# PCB_Schematic_V1.net
KiCad netlist of a schematic drawn in EasyEDA
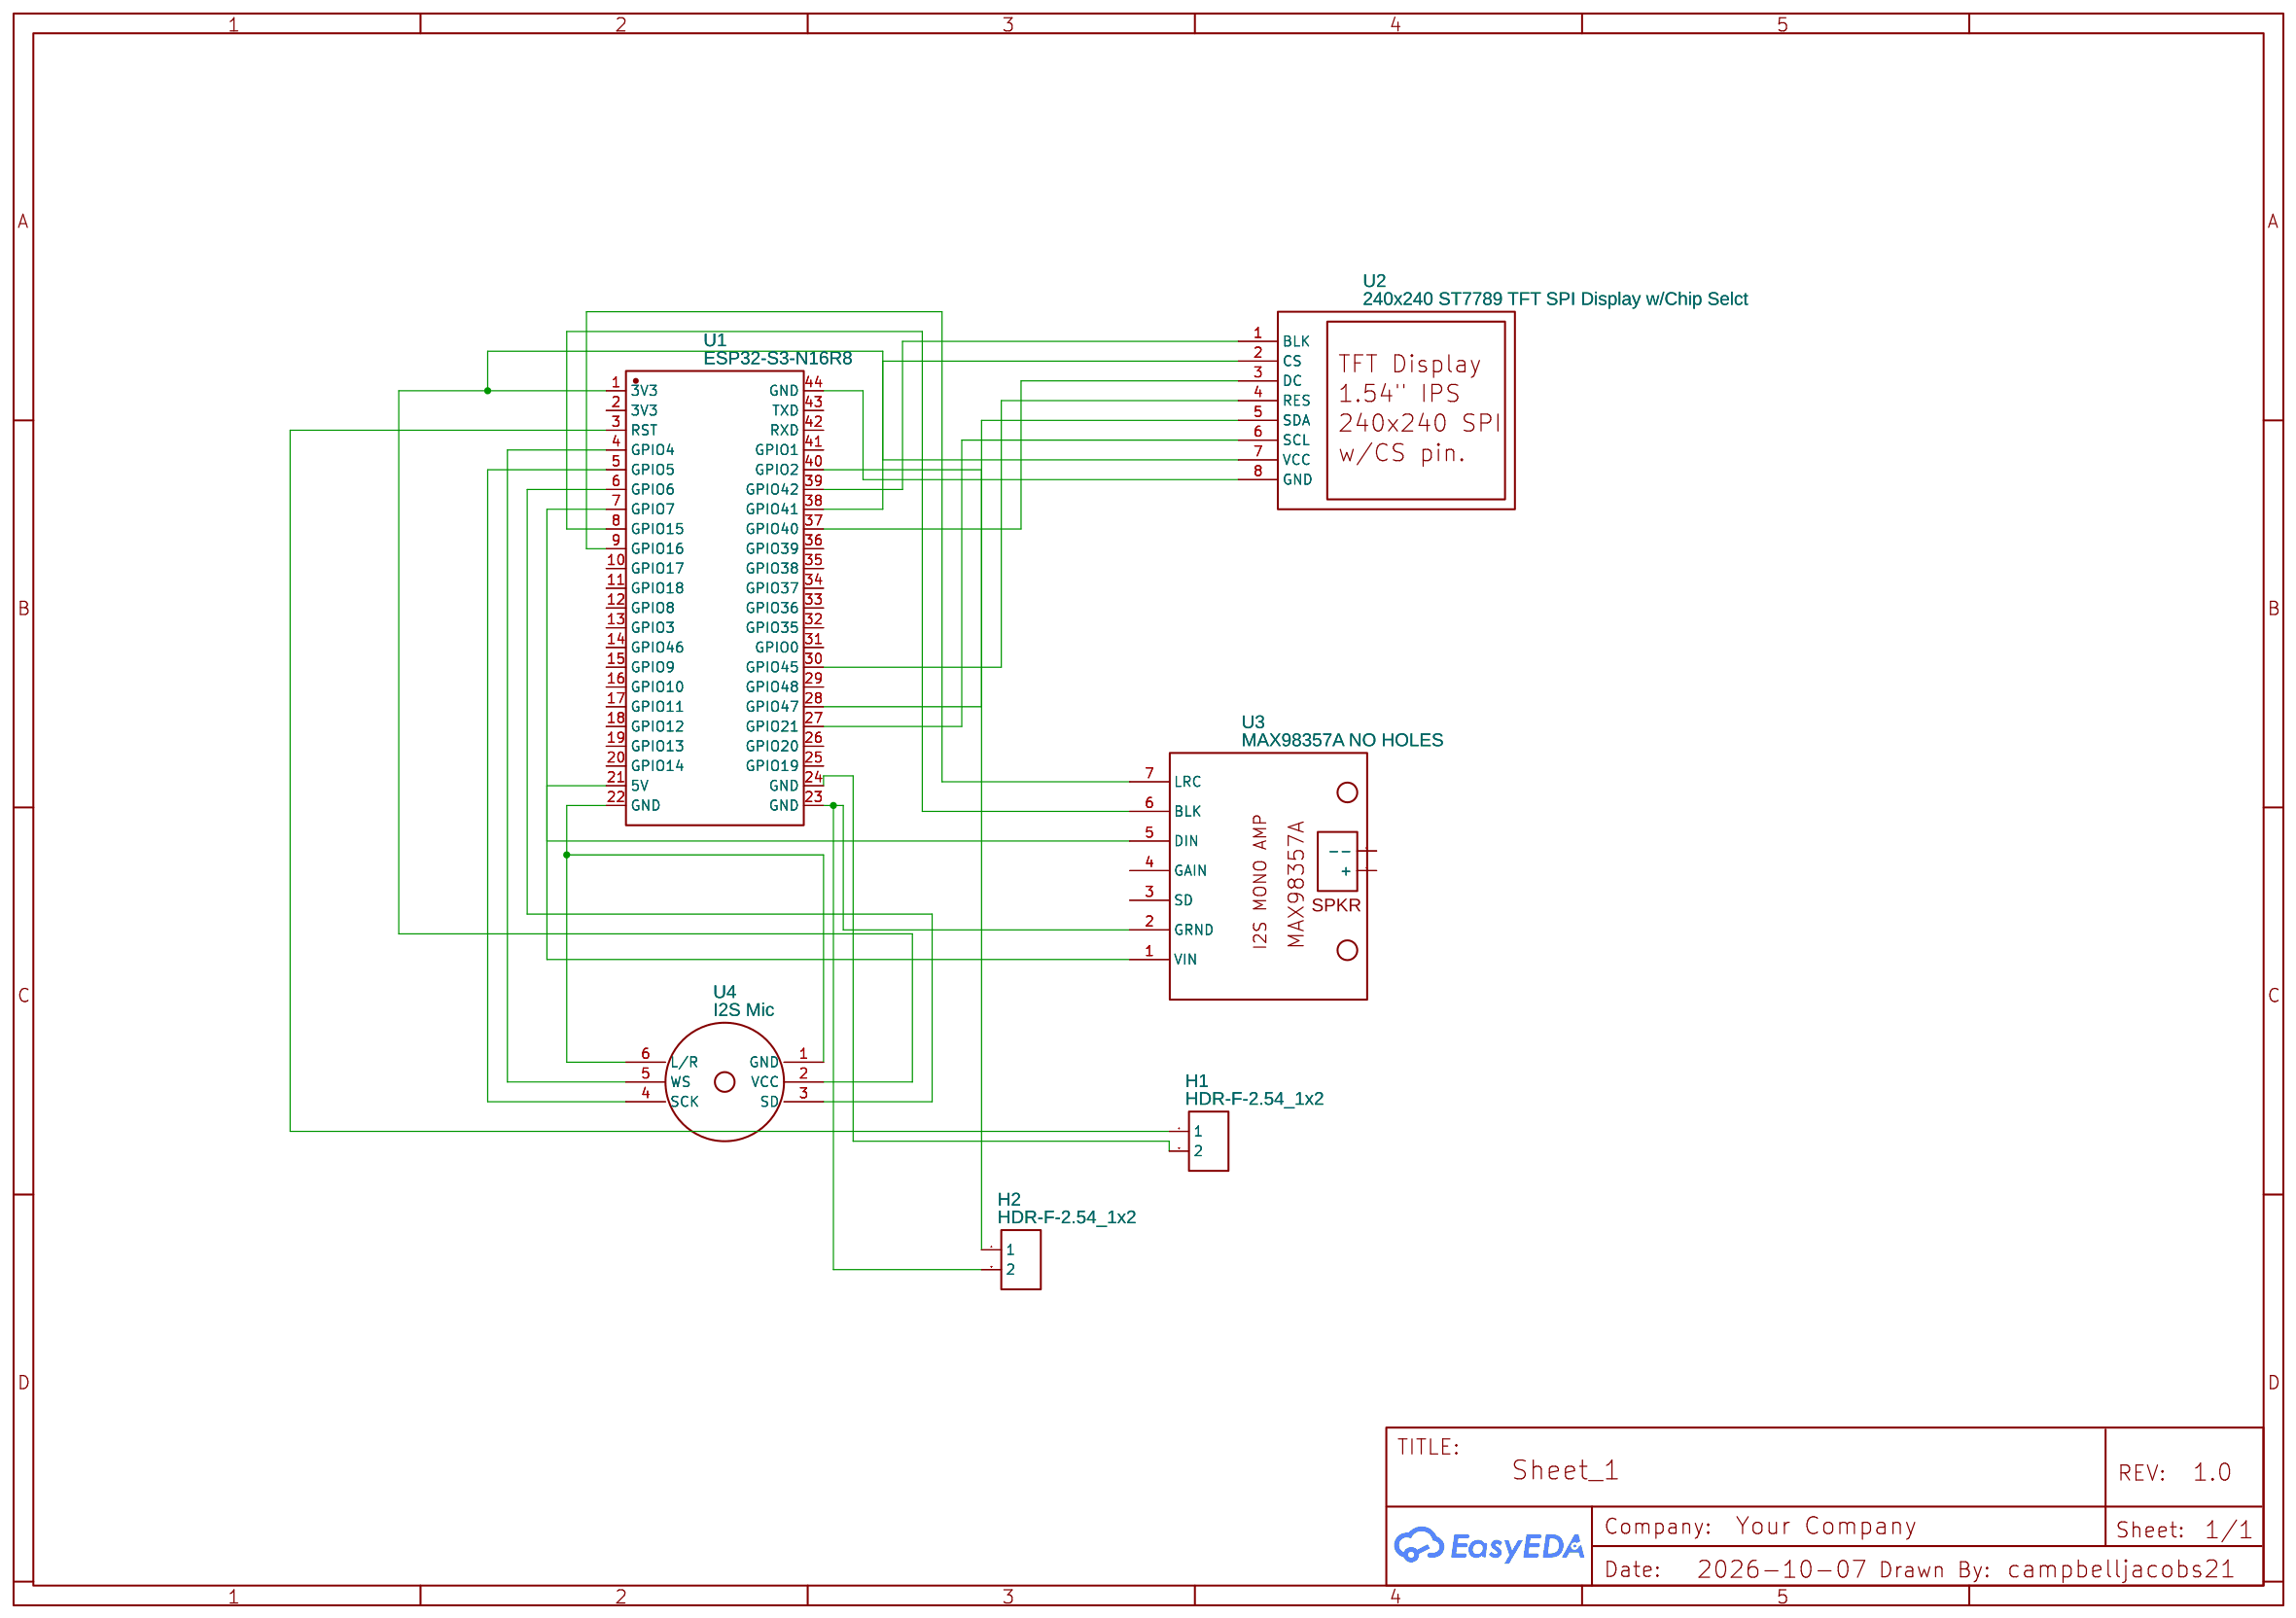
[diagram p0: schematic sheet]

(export (version "E")
  (design (tool "Eeschema 10.0.6"))
  (components
    (comp (ref "H1") (value "HDR-F-2.54_1x2") (libsource (lib "") (part "HDR-F-2.54_1x2")))
    (comp (ref "H2") (value "HDR-F-2.54_1x2") (libsource (lib "") (part "HDR-F-2.54_1x2")))
    (comp (ref "U1") (value "ESP32-S3-N16R8") (libsource (lib "") (part "ESP32-S3-N16R8")))
    (comp (ref "U2")
      (value "240x240 ST7789 TFT SPI Display w/Chip Selct")
      (libsource (lib "") (part "240x240 ST7789 TFT SPI Display w/Chip Selct"))
    )
    (comp (ref "U3")
      (value "MAX98357A NO HOLES")
      (fields (field (name "Manufacturer") "MAX98357A"))
      (libsource (lib "") (part "MAX98357A NO HOLES"))
    )
    (comp (ref "U4") (value "I2S Mic") (libsource (lib "") (part "INMP441-MEMS-I2S-MIC-MODULE")))
  )
  (nets
    (net (code "1") (name "Net-(H1-Pad2)") (class "Default")
      (node (ref "H1") (pin "2") (pinfunction "2_2") (pintype "input"))
      (node (ref "U1") (pin "24") (pinfunction "GND_24") (pintype "unspecified"))
    )
    (net (code "2") (name "Net-(U1-5V)") (class "Default")
      (node (ref "U1") (pin "21") (pinfunction "5V_21") (pintype "unspecified"))
      (node (ref "U3") (pin "1") (pinfunction "VIN_1") (pintype "unspecified"))
    )
    (net (code "3") (name "Net-(U1-GPIO2)") (class "Default")
      (node (ref "H2") (pin "1") (pinfunction "1_1") (pintype "input"))
      (node (ref "U1") (pin "40") (pinfunction "GPIO2_40") (pintype "unspecified"))
    )
    (net (code "4") (name "Net-(U1-GPIO4)") (class "Default")
      (node (ref "U1") (pin "4") (pinfunction "GPIO4_4") (pintype "unspecified"))
      (node (ref "U4") (pin "5") (pinfunction "WS_5") (pintype "unspecified"))
    )
    (net (code "5") (name "Net-(U1-GPIO5)") (class "Default")
      (node (ref "U1") (pin "5") (pinfunction "GPIO5_5") (pintype "unspecified"))
      (node (ref "U4") (pin "4") (pinfunction "SCK_4") (pintype "unspecified"))
    )
    (net (code "6") (name "Net-(U1-GPIO6)") (class "Default")
      (node (ref "U1") (pin "6") (pinfunction "GPIO6_6") (pintype "unspecified"))
      (node (ref "U4") (pin "3") (pinfunction "SD_3") (pintype "unspecified"))
    )
    (net (code "7") (name "Net-(U1-GPIO7)") (class "Default")
      (node (ref "U1") (pin "7") (pinfunction "GPIO7_7") (pintype "unspecified"))
      (node (ref "U3") (pin "5") (pinfunction "DIN_5") (pintype "unspecified"))
    )
    (net (code "8") (name "Net-(U1-GPIO15)") (class "Default")
      (node (ref "U1") (pin "8") (pinfunction "GPIO15_8") (pintype "unspecified"))
      (node (ref "U3") (pin "6") (pinfunction "BLK_6") (pintype "unspecified"))
    )
    (net (code "9") (name "Net-(U1-GPIO16)") (class "Default")
      (node (ref "U1") (pin "9") (pinfunction "GPIO16_9") (pintype "unspecified"))
      (node (ref "U3") (pin "7") (pinfunction "LRC_7") (pintype "unspecified"))
    )
    (net (code "10") (name "Net-(U1-GPIO21)") (class "Default")
      (node (ref "U1") (pin "27") (pinfunction "GPIO21_27") (pintype "unspecified"))
      (node (ref "U2") (pin "6") (pinfunction "SCL_6") (pintype "unspecified"))
    )
    (net (code "11") (name "Net-(U1-GPIO40)") (class "Default")
      (node (ref "U1") (pin "37") (pinfunction "GPIO40_37") (pintype "unspecified"))
      (node (ref "U2") (pin "3") (pinfunction "DC_3") (pintype "unspecified"))
    )
    (net (code "12") (name "Net-(U1-GPIO41)") (class "Default")
      (node (ref "U1") (pin "38") (pinfunction "GPIO41_38") (pintype "unspecified"))
      (node (ref "U2") (pin "2") (pinfunction "CS_2") (pintype "unspecified"))
    )
    (net (code "13") (name "Net-(U1-GPIO42)") (class "Default")
      (node (ref "U1") (pin "39") (pinfunction "GPIO42_39") (pintype "unspecified"))
      (node (ref "U2") (pin "1") (pinfunction "BLK_1") (pintype "unspecified"))
    )
    (net (code "14") (name "Net-(U1-GPIO45)") (class "Default")
      (node (ref "U1") (pin "30") (pinfunction "GPIO45_30") (pintype "unspecified"))
      (node (ref "U2") (pin "4") (pinfunction "RES_4") (pintype "unspecified"))
    )
    (net (code "15") (name "Net-(U1-GPIO47)") (class "Default")
      (node (ref "U1") (pin "28") (pinfunction "GPIO47_28") (pintype "unspecified"))
      (node (ref "U2") (pin "5") (pinfunction "SDA_5") (pintype "unspecified"))
    )
    (net (code "16") (name "Net-(U1-RST)") (class "Default")
      (node (ref "H1") (pin "1") (pinfunction "1_1") (pintype "input"))
      (node (ref "U1") (pin "3") (pinfunction "RST_3") (pintype "unspecified"))
    )
    (net (code "17") (name "Net-(U2-GND)") (class "Default")
      (node (ref "U1") (pin "44") (pinfunction "GND_44") (pintype "unspecified"))
      (node (ref "U2") (pin "8") (pinfunction "GND_8") (pintype "unspecified"))
    )
    (net (code "18") (name "Net-(U2-VCC)") (class "Default")
      (node (ref "U1") (pin "1") (pinfunction "3V3_1") (pintype "unspecified"))
      (node (ref "U2") (pin "7") (pinfunction "VCC_7") (pintype "unspecified"))
      (node (ref "U4") (pin "2") (pinfunction "VCC_2") (pintype "unspecified"))
    )
    (net (code "19") (name "Net-(U3-GRND)") (class "Default")
      (node (ref "H2") (pin "2") (pinfunction "2_2") (pintype "input"))
      (node (ref "U1") (pin "23") (pinfunction "GND_23") (pintype "unspecified"))
      (node (ref "U3") (pin "2") (pinfunction "GRND_2") (pintype "unspecified"))
    )
    (net (code "20") (name "Net-(U4-GND)") (class "Default")
      (node (ref "U1") (pin "22") (pinfunction "GND_22") (pintype "unspecified"))
      (node (ref "U4") (pin "1") (pinfunction "GND_1") (pintype "unspecified"))
      (node (ref "U4") (pin "6") (pinfunction "L/R_6") (pintype "unspecified"))
    )
    (net (code "21") (name "unconnected-(U1-3V3-Pad2)") (class "Default")
      (node (ref "U1") (pin "2") (pinfunction "3V3_2") (pintype "unspecified"))
    )
    (net (code "22") (name "unconnected-(U1-GPIO0-Pad31)") (class "Default")
      (node (ref "U1") (pin "31") (pinfunction "GPIO0_31") (pintype "unspecified"))
    )
    (net (code "23") (name "unconnected-(U1-GPIO1-Pad41)") (class "Default")
      (node (ref "U1") (pin "41") (pinfunction "GPIO1_41") (pintype "unspecified"))
    )
    (net (code "24") (name "unconnected-(U1-GPIO3-Pad13)") (class "Default")
      (node (ref "U1") (pin "13") (pinfunction "GPIO3_13") (pintype "unspecified"))
    )
    (net (code "25") (name "unconnected-(U1-GPIO8-Pad12)") (class "Default")
      (node (ref "U1") (pin "12") (pinfunction "GPIO8_12") (pintype "unspecified"))
    )
    (net (code "26") (name "unconnected-(U1-GPIO9-Pad15)") (class "Default")
      (node (ref "U1") (pin "15") (pinfunction "GPIO9_15") (pintype "unspecified"))
    )
    (net (code "27") (name "unconnected-(U1-GPIO10-Pad16)") (class "Default")
      (node (ref "U1") (pin "16") (pinfunction "GPIO10_16") (pintype "unspecified"))
    )
    (net (code "28") (name "unconnected-(U1-GPIO11-Pad17)") (class "Default")
      (node (ref "U1") (pin "17") (pinfunction "GPIO11_17") (pintype "unspecified"))
    )
    (net (code "29") (name "unconnected-(U1-GPIO12-Pad18)") (class "Default")
      (node (ref "U1") (pin "18") (pinfunction "GPIO12_18") (pintype "unspecified"))
    )
    (net (code "30") (name "unconnected-(U1-GPIO13-Pad19)") (class "Default")
      (node (ref "U1") (pin "19") (pinfunction "GPIO13_19") (pintype "unspecified"))
    )
    (net (code "31") (name "unconnected-(U1-GPIO14-Pad20)") (class "Default")
      (node (ref "U1") (pin "20") (pinfunction "GPIO14_20") (pintype "unspecified"))
    )
    (net (code "32") (name "unconnected-(U1-GPIO17-Pad10)") (class "Default")
      (node (ref "U1") (pin "10") (pinfunction "GPIO17_10") (pintype "unspecified"))
    )
    (net (code "33") (name "unconnected-(U1-GPIO18-Pad11)") (class "Default")
      (node (ref "U1") (pin "11") (pinfunction "GPIO18_11") (pintype "unspecified"))
    )
    (net (code "34") (name "unconnected-(U1-GPIO19-Pad25)") (class "Default")
      (node (ref "U1") (pin "25") (pinfunction "GPIO19_25") (pintype "unspecified"))
    )
    (net (code "35") (name "unconnected-(U1-GPIO20-Pad26)") (class "Default")
      (node (ref "U1") (pin "26") (pinfunction "GPIO20_26") (pintype "unspecified"))
    )
    (net (code "36") (name "unconnected-(U1-GPIO35-Pad32)") (class "Default")
      (node (ref "U1") (pin "32") (pinfunction "GPIO35_32") (pintype "unspecified"))
    )
    (net (code "37") (name "unconnected-(U1-GPIO36-Pad33)") (class "Default")
      (node (ref "U1") (pin "33") (pinfunction "GPIO36_33") (pintype "unspecified"))
    )
    (net (code "38") (name "unconnected-(U1-GPIO37-Pad34)") (class "Default")
      (node (ref "U1") (pin "34") (pinfunction "GPIO37_34") (pintype "unspecified"))
    )
    (net (code "39") (name "unconnected-(U1-GPIO38-Pad35)") (class "Default")
      (node (ref "U1") (pin "35") (pinfunction "GPIO38_35") (pintype "unspecified"))
    )
    (net (code "40") (name "unconnected-(U1-GPIO39-Pad36)") (class "Default")
      (node (ref "U1") (pin "36") (pinfunction "GPIO39_36") (pintype "unspecified"))
    )
    (net (code "41") (name "unconnected-(U1-GPIO46-Pad14)") (class "Default")
      (node (ref "U1") (pin "14") (pinfunction "GPIO46_14") (pintype "unspecified"))
    )
    (net (code "42") (name "unconnected-(U1-GPIO48-Pad29)") (class "Default")
      (node (ref "U1") (pin "29") (pinfunction "GPIO48_29") (pintype "unspecified"))
    )
    (net (code "43") (name "unconnected-(U1-RXD-Pad42)") (class "Default")
      (node (ref "U1") (pin "42") (pinfunction "RXD_42") (pintype "unspecified"))
    )
    (net (code "44") (name "unconnected-(U1-TXD-Pad43)") (class "Default")
      (node (ref "U1") (pin "43") (pinfunction "TXD_43") (pintype "unspecified"))
    )
    (net (code "45") (name "unconnected-(U3-+-Pad1)") (class "Default")
      (node (ref "U3") (pin "1") (pinfunction "+_1") (pintype "input"))
    )
    (net (code "46") (name "unconnected-(U3----Pad2)") (class "Default")
      (node (ref "U3") (pin "2") (pinfunction "--_2") (pintype "input"))
    )
    (net (code "47") (name "unconnected-(U3-GAIN-Pad4)") (class "Default")
      (node (ref "U3") (pin "4") (pinfunction "GAIN_4") (pintype "unspecified"))
    )
    (net (code "48") (name "unconnected-(U3-SD-Pad3)") (class "Default")
      (node (ref "U3") (pin "3") (pinfunction "SD_3") (pintype "unspecified"))
    )
  )
)
